# Central_Unit.net
KiCad netlist of a schematic drawn in Altium Designer
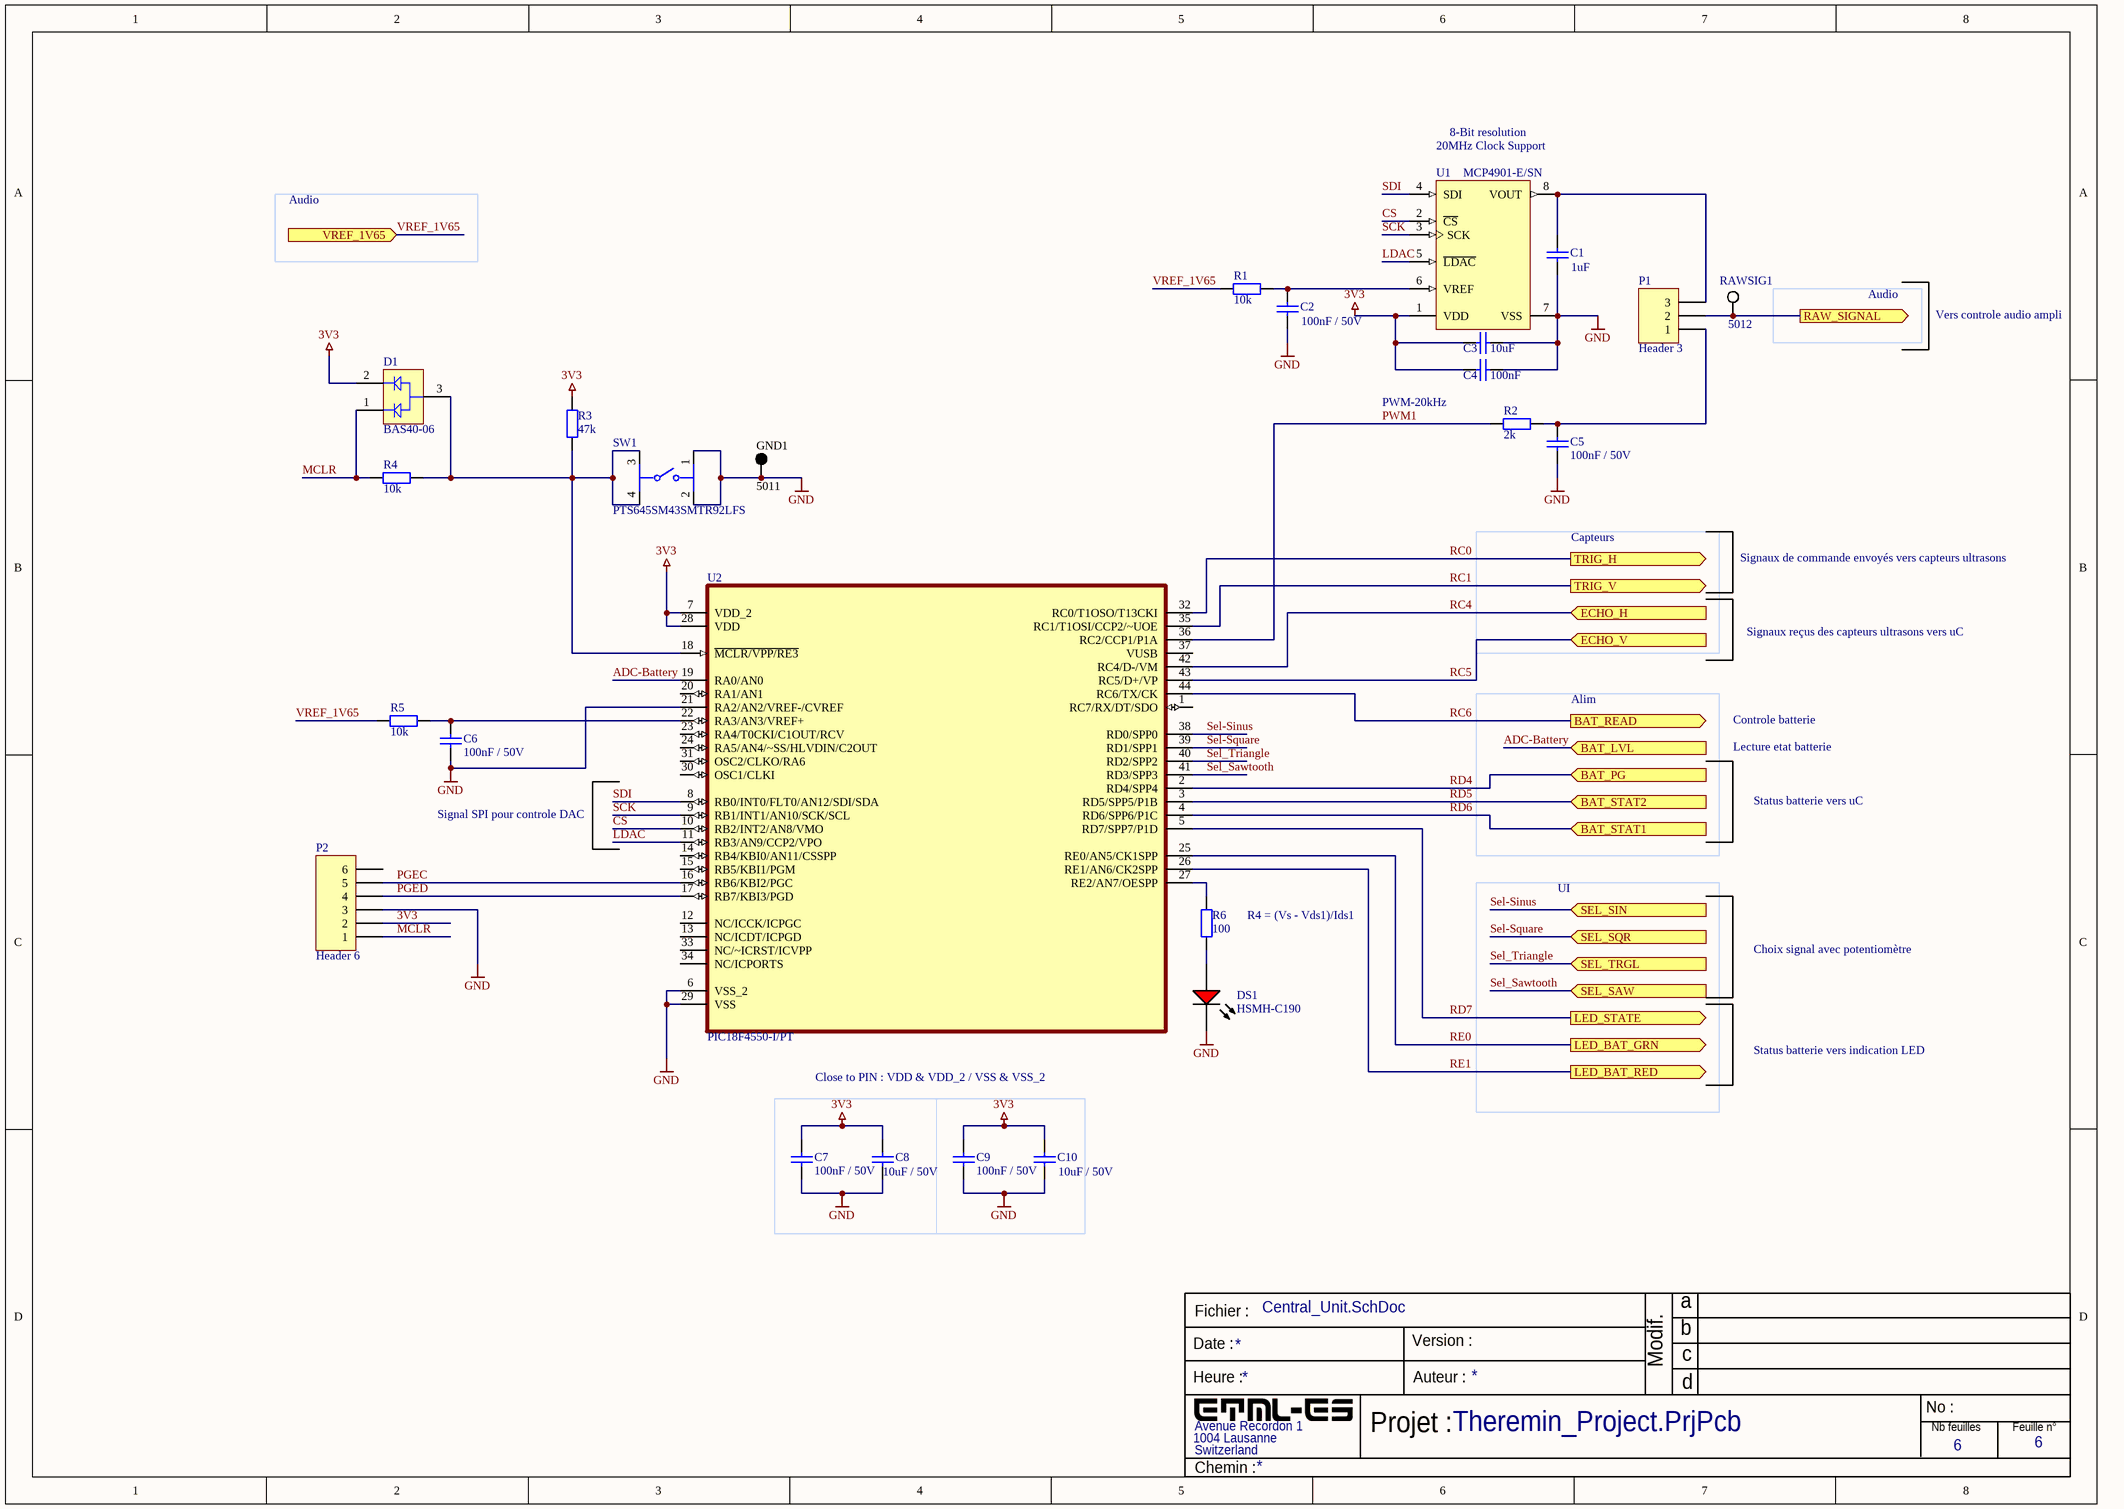
[diagram p0: Central_Unit.SchDoc]

(export (version "E")
  (design (tool "Eeschema 10.0.6"))
  (components
    (comp (ref "C1")
      (value "1uF")
      (footprint "CAPC0805")
      (description "Capacitor")
      (fields (field (name "PUBLISHER") "Altium Limited"))
      (libsource (lib "Miscellaneous Devices") (part "Cap"))
    )
    (comp (ref "C2")
      (value "100nF / 50V")
      (footprint "CAPC0805")
      (description "Capacitor")
      (fields (field (name "PUBLISHER") "Altium Limited"))
      (libsource (lib "Miscellaneous Devices") (part "Cap"))
    )
    (comp (ref "C3")
      (value "10uF")
      (footprint "CAPC0805")
      (description "Capacitor")
      (fields (field (name "PUBLISHER") "Altium Limited"))
      (libsource (lib "Miscellaneous Devices") (part "Cap"))
    )
    (comp (ref "C4")
      (value "100nF")
      (footprint "CAPC0805")
      (description "Capacitor")
      (fields (field (name "PUBLISHER") "Altium Limited"))
      (libsource (lib "Miscellaneous Devices") (part "Cap"))
    )
    (comp (ref "C5")
      (value "100nF / 50V")
      (footprint "CAPC0805")
      (description "Capacitor")
      (fields (field (name "PUBLISHER") "Altium Limited"))
      (libsource (lib "Miscellaneous Devices") (part "Cap"))
    )
    (comp (ref "C6")
      (value "100nF / 50V")
      (footprint "CAPC0805")
      (description "Capacitor")
      (fields (field (name "PUBLISHER") "Altium Limited"))
      (libsource (lib "Miscellaneous Devices") (part "Cap"))
    )
    (comp (ref "C7")
      (value "100nF / 50V")
      (footprint "CAPC0805")
      (description "Capacitor")
      (fields (field (name "PUBLISHER") "Altium Limited"))
      (libsource (lib "Miscellaneous Devices") (part "Cap"))
    )
    (comp (ref "C8")
      (value "10uF / 50V")
      (footprint "CAPC0805")
      (description "Capacitor")
      (fields (field (name "PUBLISHER") "Altium Limited"))
      (libsource (lib "Miscellaneous Devices") (part "Cap"))
    )
    (comp (ref "C9")
      (value "100nF / 50V")
      (footprint "CAPC0805")
      (description "Capacitor")
      (fields (field (name "PUBLISHER") "Altium Limited"))
      (libsource (lib "Miscellaneous Devices") (part "Cap"))
    )
    (comp (ref "C10")
      (value "10uF / 50V")
      (footprint "CAPC0805")
      (description "Capacitor")
      (fields (field (name "PUBLISHER") "Altium Limited"))
      (libsource (lib "Miscellaneous Devices") (part "Cap"))
    )
    (comp (ref "D1")
      (value "BAS40-06")
      (footprint "INF-SOT23_M")
      (description "Silicon Schottky Diode, -55 to 150 degC, SOT23, Reel, Green")
      (fields (field (name "MANUFACTURER") "Infineon"))
      (libsource (lib "Altium Content Vault") (part "INF-D_K1K2A3-3"))
    )
    (comp (ref "DS1")
      (value "HSMH-C190")
      (footprint "AVAG-HSMX-C190_V")
      (description "LED Uni-Color Red, 65 mW, 20 mA, -40 to 85 degC, 2-Pin SMD, RoHS, Tape and Reel")
      (libsource (lib "Altium Content Vault") (part "LED-RED-AK-2"))
    )
    (comp (ref "GND1")
      (value "5011")
      (footprint "KSTN-5011_V")
      (description "Test Point, Black, Through Hole, RoHS, Bulk")
      (fields (field (name "MANUFACTURER") "Keystone"))
      (libsource (lib "Altium Content Vault") (part "TESTPOINT_BLACK"))
    )
    (comp (ref "P1")
      (value "Header 3")
      (footprint "PIN-1x03_2.54")
      (description "Header, 3-Pin")
      (fields (field (name "PUBLISHER") "Altium Limited"))
      (libsource (lib "Miscellaneous Connectors") (part "Header 3"))
    )
    (comp (ref "P2")
      (value "Header 6")
      (footprint "PIN-1x06_2.54")
      (description "Header, 6-Pin")
      (fields (field (name "PUBLISHER") "Altium Limited"))
      (libsource (lib "Miscellaneous Connectors") (part "Header 6"))
    )
    (comp (ref "R1")
      (value "10k")
      (footprint "RESC0805")
      (description "Resistor")
      (libsource (lib "Support_BAT_1043") (part "RES"))
    )
    (comp (ref "R2")
      (value "2k")
      (footprint "RESC0805")
      (description "Resistor")
      (libsource (lib "Support_BAT_1043") (part "RES"))
    )
    (comp (ref "R3")
      (value "47k")
      (footprint "RESC0805")
      (description "Resistor")
      (libsource (lib "") (part "RES_1"))
    )
    (comp (ref "R4")
      (value "10k")
      (footprint "RESC0805")
      (description "Resistor")
      (libsource (lib "Support_BAT_1043") (part "RES"))
    )
    (comp (ref "R5")
      (value "10k")
      (footprint "RESC0805")
      (description "Resistor")
      (libsource (lib "Support_BAT_1043") (part "RES"))
    )
    (comp (ref "R6")
      (value "100")
      (footprint "RESC0805")
      (description "Resistor")
      (libsource (lib "") (part "RES_1"))
    )
    (comp (ref "RAWSIG1")
      (value "5012")
      (footprint "KSTN-5012_V")
      (description "Test Point, White, Through Hole, RoHS, Bulk")
      (fields (field (name "MANUFACTURER") "Keystone"))
      (libsource (lib "Altium Content Vault") (part "TESTPOINT_WHITE"))
    )
    (comp (ref "SW1")
      (value "PTS645SM43SMTR92LFS")
      (footprint "FP-PTS645SM43SMTR92LFS-MFG")
      (description "SWITCH TACTILE SPST-NO 0.05A 12V")
      (libsource (lib "Altium Content Vault") (part "1adf0dd01260c80cf25a44bfd6b99ba"))
    )
    (comp (ref "U1")
      (value "MCP4901-E/SN")
      (footprint "SOIC-SN8_N")
      (description "8-Bit DAC with SPI Interface, 8-Pin SOIC 150mil, Extended Temperature")
      (libsource (lib "Altium Content Vault") (part "CON-DAC-MCP4921-8"))
    )
    (comp (ref "U2")
      (value "PIC18F4550-I/PT")
      (footprint "TQFP80P1200X1200X120-44M")
      (description "PIC PICÂ® 18F Microcontroller IC 8-Bit 48MHz 32KB _16K x 16_ FLASH 44-TQFP _10x10_")
      (fields (field (name "MF") "Microchip"))
      (libsource (lib "PIC18F4550-I_PT") (part "PIC18F4550-I/PT"))
    )
  )
  (nets
    (net (code "1") (name "/ADC-Battery") (class "Default")
      (node (ref "U2") (pin "19") (pinfunction "RA0/AN0_19") (pintype "passive"))
    )
    (net (code "2") (name "/CS") (class "Default")
      (node (ref "U1") (pin "2") (pinfunction "~{CS}_2") (pintype "input"))
      (node (ref "U2") (pin "10") (pinfunction "RB2/INT2/AN8/VMO_10") (pintype "bidirectional"))
    )
    (net (code "3") (name "/LDAC") (class "Default")
      (node (ref "U1") (pin "5") (pinfunction "~{LDAC}_5") (pintype "input"))
      (node (ref "U2") (pin "11") (pinfunction "RB3/AN9/CCP2/VPO_11") (pintype "bidirectional"))
    )
    (net (code "4") (name "/MCLR") (class "Default")
      (node (ref "D1") (pin "1") (pinfunction "K1_1") (pintype "passive"))
      (node (ref "P2") (pin "1") (pinfunction "1_1") (pintype "passive"))
      (node (ref "R4") (pin "2") (pinfunction "2_2") (pintype "passive"))
    )
    (net (code "5") (name "/PGEC") (class "Default")
      (node (ref "P2") (pin "5") (pinfunction "5_5") (pintype "passive"))
      (node (ref "U2") (pin "16") (pinfunction "RB6/KBI2/PGC_16") (pintype "bidirectional"))
    )
    (net (code "6") (name "/PGED") (class "Default")
      (node (ref "P2") (pin "4") (pinfunction "4_4") (pintype "passive"))
      (node (ref "U2") (pin "17") (pinfunction "RB7/KBI3/PGD_17") (pintype "bidirectional"))
    )
    (net (code "7") (name "/PWM1") (class "Default")
      (node (ref "R2") (pin "2") (pinfunction "2_2") (pintype "passive"))
      (node (ref "U2") (pin "36") (pinfunction "RC2/CCP1/P1A_36") (pintype "passive"))
    )
    (net (code "8") (name "/RAW_SIGNAL") (class "Default")
      (node (ref "P1") (pin "2") (pinfunction "2_2") (pintype "passive"))
      (node (ref "RAWSIG1") (pin "1") (pinfunction "1_1") (pintype "passive"))
    )
    (net (code "9") (name "/RC0") (class "Default")
      (node (ref "U2") (pin "32") (pinfunction "RC0/T1OSO/T13CKI_32") (pintype "passive"))
    )
    (net (code "10") (name "/RC1") (class "Default")
      (node (ref "U2") (pin "35") (pinfunction "RC1/T1OSI/CCP2/~UOE_35") (pintype "passive"))
    )
    (net (code "11") (name "/RC4") (class "Default")
      (node (ref "U2") (pin "42") (pinfunction "RC4/D-/VM_42") (pintype "passive"))
    )
    (net (code "12") (name "/RC5") (class "Default")
      (node (ref "U2") (pin "43") (pinfunction "RC5/D+/VP_43") (pintype "passive"))
    )
    (net (code "13") (name "/RC6") (class "Default")
      (node (ref "U2") (pin "44") (pinfunction "RC6/TX/CK_44") (pintype "passive"))
    )
    (net (code "14") (name "/RD4") (class "Default")
      (node (ref "U2") (pin "2") (pinfunction "RD4/SPP4_2") (pintype "passive"))
    )
    (net (code "15") (name "/RD5") (class "Default")
      (node (ref "U2") (pin "3") (pinfunction "RD5/SPP5/P1B_3") (pintype "passive"))
    )
    (net (code "16") (name "/RD6") (class "Default")
      (node (ref "U2") (pin "4") (pinfunction "RD6/SPP6/P1C_4") (pintype "passive"))
    )
    (net (code "17") (name "/RD7") (class "Default")
      (node (ref "U2") (pin "5") (pinfunction "RD7/SPP7/P1D_5") (pintype "passive"))
    )
    (net (code "18") (name "/RE0") (class "Default")
      (node (ref "U2") (pin "25") (pinfunction "RE0/AN5/CK1SPP_25") (pintype "passive"))
    )
    (net (code "19") (name "/RE1") (class "Default")
      (node (ref "U2") (pin "26") (pinfunction "RE1/AN6/CK2SPP_26") (pintype "passive"))
    )
    (net (code "20") (name "/SCK") (class "Default")
      (node (ref "U1") (pin "3") (pinfunction "SCK_3") (pintype "input"))
      (node (ref "U2") (pin "9") (pinfunction "RB1/INT1/AN10/SCK/SCL_9") (pintype "bidirectional"))
    )
    (net (code "21") (name "/SDI") (class "Default")
      (node (ref "U1") (pin "4") (pinfunction "SDI_4") (pintype "input"))
      (node (ref "U2") (pin "8") (pinfunction "RB0/INT0/FLT0/AN12/SDI/SDA_8") (pintype "bidirectional"))
    )
    (net (code "22") (name "/Sel-Sinus") (class "Default")
      (node (ref "U2") (pin "38") (pinfunction "RD0/SPP0_38") (pintype "passive"))
    )
    (net (code "23") (name "/Sel-Square") (class "Default")
      (node (ref "U2") (pin "39") (pinfunction "RD1/SPP1_39") (pintype "passive"))
    )
    (net (code "24") (name "/Sel_Sawtooth") (class "Default")
      (node (ref "U2") (pin "41") (pinfunction "RD3/SPP3_41") (pintype "passive"))
    )
    (net (code "25") (name "/Sel_Triangle") (class "Default")
      (node (ref "U2") (pin "40") (pinfunction "RD2/SPP2_40") (pintype "passive"))
    )
    (net (code "26") (name "/VREF_1V65") (class "Default")
      (node (ref "R1") (pin "2") (pinfunction "2_2") (pintype "passive"))
      (node (ref "R5") (pin "2") (pinfunction "2_2") (pintype "passive"))
    )
    (net (code "27") (name "3V3") (class "Default")
      (node (ref "C10") (pin "1") (pinfunction "1_1") (pintype "passive"))
      (node (ref "C3") (pin "1") (pinfunction "1_1") (pintype "passive"))
      (node (ref "C4") (pin "1") (pinfunction "1_1") (pintype "passive"))
      (node (ref "C7") (pin "1") (pinfunction "1_1") (pintype "passive"))
      (node (ref "C8") (pin "1") (pinfunction "1_1") (pintype "passive"))
      (node (ref "C9") (pin "1") (pinfunction "1_1") (pintype "passive"))
      (node (ref "D1") (pin "2") (pinfunction "K2_2") (pintype "passive"))
      (node (ref "P2") (pin "2") (pinfunction "2_2") (pintype "passive"))
      (node (ref "R3") (pin "1") (pinfunction "1_1") (pintype "passive"))
      (node (ref "U1") (pin "1") (pinfunction "VDD_1") (pintype "power_in"))
      (node (ref "U2") (pin "28") (pinfunction "VDD_28") (pintype "power_in"))
      (node (ref "U2") (pin "7") (pinfunction "VDD_2_7") (pintype "power_in"))
    )
    (net (code "28") (name "GND") (class "Default")
      (node (ref "C1") (pin "2") (pinfunction "2_2") (pintype "passive"))
      (node (ref "C10") (pin "2") (pinfunction "2_2") (pintype "passive"))
      (node (ref "C2") (pin "2") (pinfunction "2_2") (pintype "passive"))
      (node (ref "C3") (pin "2") (pinfunction "2_2") (pintype "passive"))
      (node (ref "C4") (pin "2") (pinfunction "2_2") (pintype "passive"))
      (node (ref "C5") (pin "2") (pinfunction "2_2") (pintype "passive"))
      (node (ref "C6") (pin "2") (pinfunction "2_2") (pintype "passive"))
      (node (ref "C7") (pin "2") (pinfunction "2_2") (pintype "passive"))
      (node (ref "C8") (pin "2") (pinfunction "2_2") (pintype "passive"))
      (node (ref "C9") (pin "2") (pinfunction "2_2") (pintype "passive"))
      (node (ref "DS1") (pin "2") (pinfunction "K_2") (pintype "passive"))
      (node (ref "GND1") (pin "1") (pinfunction "1_1") (pintype "passive"))
      (node (ref "P2") (pin "3") (pinfunction "3_3") (pintype "passive"))
      (node (ref "SW1") (pin "1") (pinfunction "1_1") (pintype "passive"))
      (node (ref "SW1") (pin "2") (pinfunction "2_2") (pintype "passive"))
      (node (ref "U1") (pin "7") (pinfunction "VSS_7") (pintype "power_in"))
      (node (ref "U2") (pin "21") (pinfunction "RA2/AN2/VREF-/CVREF_21") (pintype "passive"))
      (node (ref "U2") (pin "29") (pinfunction "VSS_29") (pintype "power_in"))
      (node (ref "U2") (pin "6") (pinfunction "VSS_2_6") (pintype "power_in"))
    )
    (net (code "29") (name "Net-(C5-Pad1)") (class "Default")
      (node (ref "C5") (pin "1") (pinfunction "1_1") (pintype "passive"))
      (node (ref "P1") (pin "1") (pinfunction "1_1") (pintype "passive"))
      (node (ref "R2") (pin "1") (pinfunction "1_1") (pintype "passive"))
    )
    (net (code "30") (name "Net-(D1-A)") (class "Default")
      (node (ref "D1") (pin "3") (pinfunction "A_3") (pintype "passive"))
      (node (ref "R3") (pin "2") (pinfunction "2_2") (pintype "passive"))
      (node (ref "R4") (pin "1") (pinfunction "1_1") (pintype "passive"))
      (node (ref "SW1") (pin "3") (pinfunction "3_3") (pintype "passive"))
      (node (ref "SW1") (pin "4") (pinfunction "4_4") (pintype "passive"))
      (node (ref "U2") (pin "18") (pinfunction "~{MCLR/VPP/RE3}_18") (pintype "input"))
    )
    (net (code "31") (name "Net-(DS1-A)") (class "Default")
      (node (ref "DS1") (pin "1") (pinfunction "A_1") (pintype "passive"))
      (node (ref "R6") (pin "2") (pinfunction "2_2") (pintype "passive"))
    )
    (net (code "32") (name "Net-(U1-VOUT)") (class "Default")
      (node (ref "C1") (pin "1") (pinfunction "1_1") (pintype "passive"))
      (node (ref "P1") (pin "3") (pinfunction "3_3") (pintype "passive"))
      (node (ref "U1") (pin "8") (pinfunction "VOUT_8") (pintype "output"))
    )
    (net (code "33") (name "Net-(U1-VREF)") (class "Default")
      (node (ref "C2") (pin "1") (pinfunction "1_1") (pintype "passive"))
      (node (ref "R1") (pin "1") (pinfunction "1_1") (pintype "passive"))
      (node (ref "U1") (pin "6") (pinfunction "VREF_6") (pintype "input"))
    )
    (net (code "34") (name "Net-(U2-RA3{slash}AN3{slash}VREF+)") (class "Default")
      (node (ref "C6") (pin "1") (pinfunction "1_1") (pintype "passive"))
      (node (ref "R5") (pin "1") (pinfunction "1_1") (pintype "passive"))
      (node (ref "U2") (pin "22") (pinfunction "RA3/AN3/VREF+_22") (pintype "bidirectional"))
    )
    (net (code "35") (name "Net-(U2-RE2{slash}AN7{slash}OESPP)") (class "Default")
      (node (ref "R6") (pin "1") (pinfunction "1_1") (pintype "passive"))
      (node (ref "U2") (pin "27") (pinfunction "RE2/AN7/OESPP_27") (pintype "passive"))
    )
    (net (code "36") (name "unconnected-(P2-Pad6)") (class "Default")
      (node (ref "P2") (pin "6") (pinfunction "6_6") (pintype "passive"))
    )
    (net (code "37") (name "unconnected-(U2-NC{slash}ICCK{slash}ICPGC-Pad12)") (class "Default")
      (node (ref "U2") (pin "12") (pinfunction "NC/ICCK/ICPGC_12") (pintype "passive"))
    )
    (net (code "38") (name "unconnected-(U2-NC{slash}ICDT{slash}ICPGD-Pad13)") (class "Default")
      (node (ref "U2") (pin "13") (pinfunction "NC/ICDT/ICPGD_13") (pintype "passive"))
    )
    (net (code "39") (name "unconnected-(U2-NC{slash}ICPORTS-Pad34)") (class "Default")
      (node (ref "U2") (pin "34") (pinfunction "NC/ICPORTS_34") (pintype "passive"))
    )
    (net (code "40") (name "unconnected-(U2-NC{slash}~ICRST{slash}ICVPP-Pad33)") (class "Default")
      (node (ref "U2") (pin "33") (pinfunction "NC/~ICRST/ICVPP_33") (pintype "passive"))
    )
    (net (code "41") (name "unconnected-(U2-OSC1{slash}CLKI-Pad30)") (class "Default")
      (node (ref "U2") (pin "30") (pinfunction "OSC1/CLKI_30") (pintype "bidirectional"))
    )
    (net (code "42") (name "unconnected-(U2-OSC2{slash}CLKO{slash}RA6-Pad31)") (class "Default")
      (node (ref "U2") (pin "31") (pinfunction "OSC2/CLKO/RA6_31") (pintype "bidirectional"))
    )
    (net (code "43") (name "unconnected-(U2-RA1{slash}AN1-Pad20)") (class "Default")
      (node (ref "U2") (pin "20") (pinfunction "RA1/AN1_20") (pintype "bidirectional"))
    )
    (net (code "44") (name "unconnected-(U2-RA4{slash}T0CKI{slash}C1OUT{slash}RCV-Pad23)") (class "Default")
      (node (ref "U2") (pin "23") (pinfunction "RA4/T0CKI/C1OUT/RCV_23") (pintype "bidirectional"))
    )
    (net (code "45") (name "unconnected-(U2-RA5{slash}AN4{slash}~SS{slash}HLVDIN{slash}C2OUT-Pad24)") (class "Default")
      (node (ref "U2") (pin "24") (pinfunction "RA5/AN4/~SS/HLVDIN/C2OUT_24") (pintype "bidirectional"))
    )
    (net (code "46") (name "unconnected-(U2-RB4{slash}KBI0{slash}AN11{slash}CSSPP-Pad14)") (class "Default")
      (node (ref "U2") (pin "14") (pinfunction "RB4/KBI0/AN11/CSSPP_14") (pintype "bidirectional"))
    )
    (net (code "47") (name "unconnected-(U2-RB5{slash}KBI1{slash}PGM-Pad15)") (class "Default")
      (node (ref "U2") (pin "15") (pinfunction "RB5/KBI1/PGM_15") (pintype "bidirectional"))
    )
    (net (code "48") (name "unconnected-(U2-RC7{slash}RX{slash}DT{slash}SDO-Pad1)") (class "Default")
      (node (ref "U2") (pin "1") (pinfunction "RC7/RX/DT/SDO_1") (pintype "bidirectional"))
    )
    (net (code "49") (name "unconnected-(U2-VUSB-Pad37)") (class "Default")
      (node (ref "U2") (pin "37") (pinfunction "VUSB_37") (pintype "passive"))
    )
  )
)
